# USBPowerCut.net
KiCad netlist of a schematic drawn in EAGLE
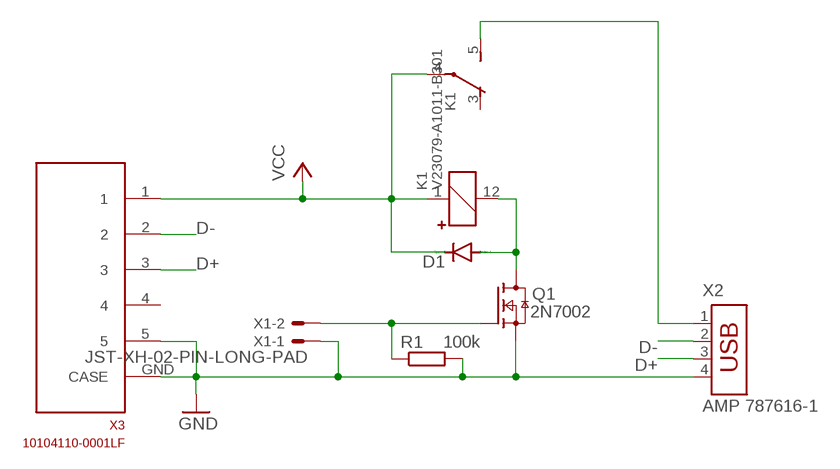
[diagram p0: schematic, sheet 1]

(export (version "E")
  (design (tool "Eeschema 10.0.6"))
  (components
    (comp (ref "D1")
      (value "1N4148")
      (footprint "eagle-import:DO35-10")
      (libsource (lib "eagle-import") (part "1N4148DO35-10"))
    )
    (comp (ref "K1")
      (value "V23079-A1011-B301")
      (footprint "eagle-import:V23079A")
      (libsource (lib "eagle-import") (part "V23079A"))
    )
    (comp (ref "Q1")
      (value "2N7002")
      (footprint "eagle-import:SOT23")
      (libsource (lib "eagle-import") (part "2N7002F"))
    )
    (comp (ref "R1")
      (value "100k")
      (footprint "eagle-import:R0805")
      (libsource (lib "eagle-import") (part "R-EU_R0805"))
    )
    (comp (ref "X1")
      (value "JST-XH-02-PIN-LONG-PAD")
      (footprint "eagle-import:JST-XH-02-PACKAGE-LONG-PAD")
      (libsource (lib "eagle-import") (part "JST-XH-02-PIN-LONG-PAD"))
    )
    (comp (ref "X2")
      (value "AMP 787616-1")
      (footprint "eagle-import:USB")
      (libsource (lib "eagle-import") (part "USB-787616"))
    )
    (comp (ref "X3")
      (value "10104110-0001LF")
      (footprint "eagle-import:MICRO_USB")
      (fields (field (name "MF") "Amphenol ICC"))
      (libsource (lib "eagle-import") (part "10104110-0001LF"))
    )
  )
  (nets
    (net (code "1") (name "/D+") (class "Default")
      (node (ref "X2") (pin "3") (pinfunction "3_3") (pintype "passive"))
      (node (ref "X3") (pin "3") (pinfunction "3_3") (pintype "bidirectional"))
    )
    (net (code "2") (name "/D-") (class "Default")
      (node (ref "X2") (pin "2") (pinfunction "2_2") (pintype "passive"))
      (node (ref "X3") (pin "2") (pinfunction "2_2") (pintype "bidirectional"))
    )
    (net (code "3") (name "GND") (class "Default")
      (node (ref "Q1") (pin "2") (pinfunction "S_2") (pintype "passive"))
      (node (ref "R1") (pin "2") (pinfunction "2_2") (pintype "passive"))
      (node (ref "X1") (pin "1") (pinfunction "S_1") (pintype "passive"))
      (node (ref "X2") (pin "4") (pinfunction "4_4") (pintype "passive"))
      (node (ref "X3") (pin "5") (pinfunction "5_5") (pintype "bidirectional"))
      (node (ref "X3") (pin "GND") (pinfunction "CASE_GND") (pintype "bidirectional"))
    )
    (net (code "4") (name "Net-(K1A--)") (class "Default")
      (node (ref "D1") (pin "A") (pinfunction "A_A") (pintype "passive"))
      (node (ref "K1") (pin "12") (pinfunction "-_12") (pintype "passive"))
      (node (ref "Q1") (pin "3") (pinfunction "D_3") (pintype "passive"))
    )
    (net (code "5") (name "Net-(K1B-S)") (class "Default")
      (node (ref "K1") (pin "5") (pinfunction "S_5") (pintype "passive"))
      (node (ref "X2") (pin "1") (pinfunction "1_1") (pintype "passive"))
    )
    (net (code "6") (name "Net-(Q1-G)") (class "Default")
      (node (ref "Q1") (pin "1") (pinfunction "G_1") (pintype "passive"))
      (node (ref "R1") (pin "1") (pinfunction "1_1") (pintype "passive"))
      (node (ref "X1") (pin "2") (pinfunction "S_2") (pintype "passive"))
    )
    (net (code "7") (name "VCC") (class "Default")
      (node (ref "D1") (pin "C") (pinfunction "C_C") (pintype "passive"))
      (node (ref "K1") (pin "1") (pinfunction "+_1") (pintype "passive"))
      (node (ref "K1") (pin "4") (pinfunction "P_4") (pintype "passive"))
      (node (ref "X3") (pin "1") (pinfunction "1_1") (pintype "bidirectional"))
    )
    (net (code "8") (name "unconnected-(K1B-O-Pad3)") (class "Default")
      (node (ref "K1") (pin "3") (pinfunction "O_3") (pintype "passive"))
    )
    (net (code "9") (name "unconnected-(X3-Pad4)") (class "Default")
      (node (ref "X3") (pin "4") (pinfunction "4_4") (pintype "bidirectional"))
    )
  )
)
